# photon_pixel_shield_v1.net
KiCad netlist of a schematic drawn in EAGLE
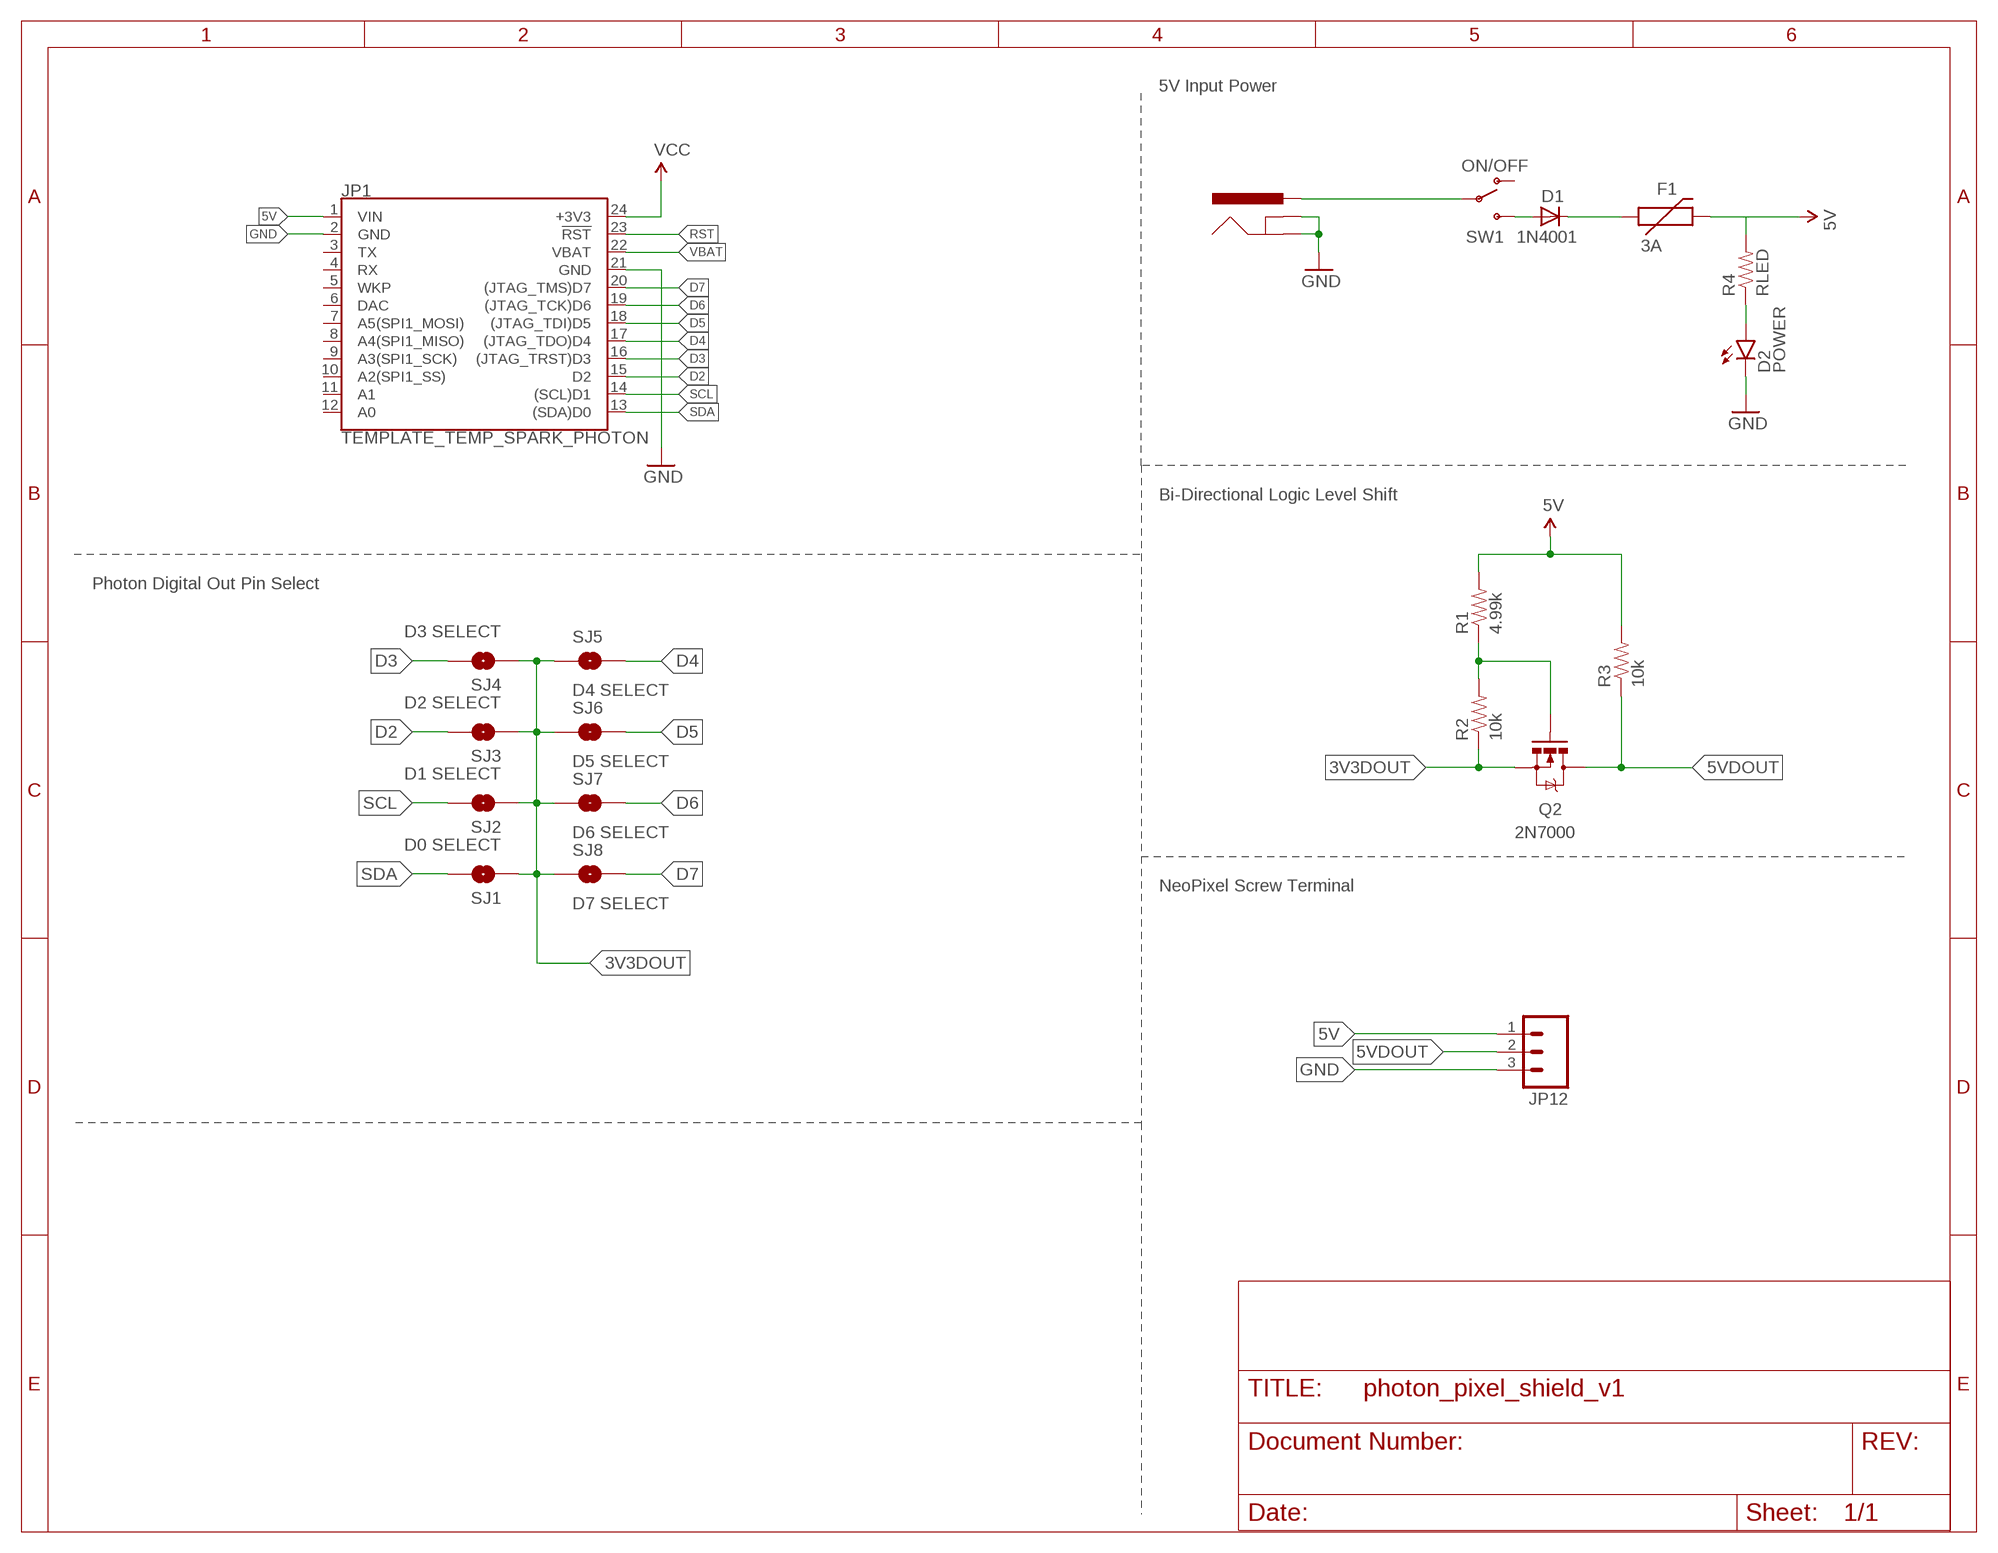
[diagram p0: schematic, sheet 1]

(export (version "E")
  (design (tool "Eeschema 10.0.6"))
  (components
    (comp (ref "D1")
      (value "1N4001")
      (footprint "eagle-import:DIODE-0.4")
      (libsource (lib "eagle-import") (part "DIODEPTH"))
    )
    (comp (ref "D2")
      (value "POWER")
      (footprint "eagle-import:LED3MM")
      (libsource (lib "eagle-import") (part "LED3MM"))
    )
    (comp (ref "F1")
      (value "3A")
      (footprint "eagle-import:PTC")
      (libsource (lib "eagle-import") (part "PTCPTH"))
    )
    (comp (ref "J1")
      (value "POWER_JACKPTH")
      (footprint "eagle-import:POWER_JACK_PTH")
      (libsource (lib "eagle-import") (part "POWER_JACKPTH"))
    )
    (comp (ref "JP1")
      (value "TEMPLATE_TEMP_SPARK_PHOTON")
      (footprint "eagle-import:TEMPLATE_TEMP_SPARK_PHOTON")
      (libsource (lib "eagle-import") (part "TEMPLATE_TEMP_SPARK_PHOTON"))
    )
    (comp (ref "JP12")
      (value "M03SCREW")
      (footprint "eagle-import:SCREWTERMINAL-3.5MM-3")
      (libsource (lib "eagle-import") (part "M03SCREW"))
    )
    (comp (ref "Q2")
      (value "2N7000")
      (footprint "eagle-import:TO-92")
      (libsource (lib "eagle-import") (part "MOSFET-NCHANNEL2N7000"))
    )
    (comp (ref "R1")
      (value "4.99k")
      (footprint "eagle-import:AXIAL-0.3")
      (libsource (lib "eagle-import") (part "10KOHM-1/4W-1%(PTH)HORIZ"))
    )
    (comp (ref "R2")
      (value "10k")
      (footprint "eagle-import:AXIAL-0.3")
      (libsource (lib "eagle-import") (part "10KOHM-1/4W-1%(PTH)HORIZ"))
    )
    (comp (ref "R3")
      (value "10k")
      (footprint "eagle-import:AXIAL-0.3")
      (libsource (lib "eagle-import") (part "10KOHM-1/4W-1%(PTH)HORIZ"))
    )
    (comp (ref "R4")
      (value "RLED")
      (footprint "eagle-import:AXIAL-0.3")
      (libsource (lib "eagle-import") (part "10KOHM-1/4W-1%(PTH)HORIZ"))
    )
    (comp (ref "SJ1")
      (value "D0 SELECT")
      (footprint "eagle-import:SJ_2S-NO")
      (libsource (lib "eagle-import") (part "SOLDERJUMPERNO"))
    )
    (comp (ref "SJ2")
      (value "D1 SELECT")
      (footprint "eagle-import:SJ_2S-NO")
      (libsource (lib "eagle-import") (part "SOLDERJUMPERNO"))
    )
    (comp (ref "SJ3")
      (value "D2 SELECT")
      (footprint "eagle-import:SJ_2S-NO")
      (libsource (lib "eagle-import") (part "SOLDERJUMPERNO"))
    )
    (comp (ref "SJ4")
      (value "D3 SELECT")
      (footprint "eagle-import:SJ_2S-NO")
      (libsource (lib "eagle-import") (part "SOLDERJUMPERNO"))
    )
    (comp (ref "SJ5")
      (value "D4 SELECT")
      (footprint "eagle-import:SJ_2S-NO")
      (libsource (lib "eagle-import") (part "SOLDERJUMPERNO"))
    )
    (comp (ref "SJ6")
      (value "D5 SELECT")
      (footprint "eagle-import:SJ_2S-NO")
      (libsource (lib "eagle-import") (part "SOLDERJUMPERNO"))
    )
    (comp (ref "SJ7")
      (value "D6 SELECT")
      (footprint "eagle-import:SJ_2S-NO")
      (libsource (lib "eagle-import") (part "SOLDERJUMPERNO"))
    )
    (comp (ref "SJ8")
      (value "D7 SELECT")
      (footprint "eagle-import:SJ_2S-NO")
      (libsource (lib "eagle-import") (part "SOLDERJUMPERNO"))
    )
    (comp (ref "SW1")
      (value "ON/OFF")
      (footprint "eagle-import:SWITCH-SPST")
      (libsource (lib "eagle-import") (part "SWITCH-SPSTPTH"))
    )
  )
  (nets
    (net (code "1") (name "3V3DOUT") (class "Default")
      (node (ref "Q2") (pin "1") (pinfunction "S_1") (pintype "passive"))
      (node (ref "R2") (pin "P$1") (pinfunction "1_P$1") (pintype "passive"))
      (node (ref "SJ1") (pin "1") (pinfunction "1_1") (pintype "passive"))
      (node (ref "SJ2") (pin "1") (pinfunction "1_1") (pintype "passive"))
      (node (ref "SJ3") (pin "1") (pinfunction "1_1") (pintype "passive"))
      (node (ref "SJ4") (pin "1") (pinfunction "1_1") (pintype "passive"))
      (node (ref "SJ5") (pin "1") (pinfunction "1_1") (pintype "passive"))
      (node (ref "SJ6") (pin "1") (pinfunction "1_1") (pintype "passive"))
      (node (ref "SJ7") (pin "1") (pinfunction "1_1") (pintype "passive"))
      (node (ref "SJ8") (pin "1") (pinfunction "1_1") (pintype "passive"))
    )
    (net (code "2") (name "5V") (class "Default")
      (node (ref "F1") (pin "P$2") (pinfunction "2_P$2") (pintype "bidirectional"))
      (node (ref "JP1") (pin "1") (pinfunction "VIN_1") (pintype "bidirectional"))
      (node (ref "JP12") (pin "1") (pinfunction "1_1") (pintype "passive"))
      (node (ref "R1") (pin "P$2") (pinfunction "2_P$2") (pintype "passive"))
      (node (ref "R3") (pin "P$2") (pinfunction "2_P$2") (pintype "passive"))
      (node (ref "R4") (pin "P$2") (pinfunction "2_P$2") (pintype "passive"))
    )
    (net (code "3") (name "5VDOUT") (class "Default")
      (node (ref "JP12") (pin "2") (pinfunction "2_2") (pintype "passive"))
      (node (ref "Q2") (pin "3") (pinfunction "D_3") (pintype "passive"))
      (node (ref "R3") (pin "P$1") (pinfunction "1_P$1") (pintype "passive"))
    )
    (net (code "4") (name "D2") (class "Default")
      (node (ref "JP1") (pin "15") (pinfunction "D2_15") (pintype "bidirectional"))
      (node (ref "SJ3") (pin "2") (pinfunction "2_2") (pintype "passive"))
    )
    (net (code "5") (name "D3") (class "Default")
      (node (ref "JP1") (pin "16") (pinfunction "(JTAG_TRST)D3_16") (pintype "bidirectional"))
      (node (ref "SJ4") (pin "2") (pinfunction "2_2") (pintype "passive"))
    )
    (net (code "6") (name "D4") (class "Default")
      (node (ref "JP1") (pin "17") (pinfunction "(JTAG_TDO)D4_17") (pintype "bidirectional"))
      (node (ref "SJ5") (pin "2") (pinfunction "2_2") (pintype "passive"))
    )
    (net (code "7") (name "D5") (class "Default")
      (node (ref "JP1") (pin "18") (pinfunction "(JTAG_TDI)D5_18") (pintype "bidirectional"))
      (node (ref "SJ6") (pin "2") (pinfunction "2_2") (pintype "passive"))
    )
    (net (code "8") (name "D6") (class "Default")
      (node (ref "JP1") (pin "19") (pinfunction "(JTAG_TCK)D6_19") (pintype "bidirectional"))
      (node (ref "SJ7") (pin "2") (pinfunction "2_2") (pintype "passive"))
    )
    (net (code "9") (name "D7") (class "Default")
      (node (ref "JP1") (pin "20") (pinfunction "(JTAG_TMS)D7_20") (pintype "bidirectional"))
      (node (ref "SJ8") (pin "2") (pinfunction "2_2") (pintype "passive"))
    )
    (net (code "10") (name "GND") (class "Default")
      (node (ref "D2") (pin "K") (pinfunction "C_K") (pintype "passive"))
      (node (ref "J1") (pin "GND") (pinfunction "GND_GND") (pintype "bidirectional"))
      (node (ref "J1") (pin "GNDBREAK") (pinfunction "GNDBREAK_GNDBREAK") (pintype "bidirectional"))
      (node (ref "JP1") (pin "2") (pinfunction "GND_2") (pintype "bidirectional"))
      (node (ref "JP1") (pin "21") (pinfunction "GND_21") (pintype "bidirectional"))
      (node (ref "JP12") (pin "3") (pinfunction "3_3") (pintype "passive"))
    )
    (net (code "11") (name "Net-(F1-1)") (class "Default")
      (node (ref "D1") (pin "C") (pinfunction "C_C") (pintype "passive"))
      (node (ref "F1") (pin "P$1") (pinfunction "1_P$1") (pintype "bidirectional"))
    )
    (net (code "12") (name "Net-(Q2-G)") (class "Default")
      (node (ref "Q2") (pin "2") (pinfunction "G_2") (pintype "passive"))
      (node (ref "R1") (pin "P$1") (pinfunction "1_P$1") (pintype "passive"))
      (node (ref "R2") (pin "P$2") (pinfunction "2_P$2") (pintype "passive"))
    )
    (net (code "13") (name "Net-(R4-1)") (class "Default")
      (node (ref "D2") (pin "A") (pinfunction "A_A") (pintype "passive"))
      (node (ref "R4") (pin "P$1") (pinfunction "1_P$1") (pintype "passive"))
    )
    (net (code "14") (name "Net-(SW1-P)") (class "Default")
      (node (ref "J1") (pin "PWR") (pinfunction "PWR_PWR") (pintype "bidirectional"))
      (node (ref "SW1") (pin "2") (pinfunction "P_2") (pintype "passive"))
    )
    (net (code "15") (name "Net-(SW1-S)") (class "Default")
      (node (ref "D1") (pin "A") (pinfunction "A_A") (pintype "passive"))
      (node (ref "SW1") (pin "3") (pinfunction "S_3") (pintype "passive"))
    )
    (net (code "16") (name "RST") (class "Default")
      (node (ref "JP1") (pin "23") (pinfunction "~{RST}_23") (pintype "bidirectional"))
    )
    (net (code "17") (name "SCL") (class "Default")
      (node (ref "JP1") (pin "14") (pinfunction "(SCL)D1_14") (pintype "bidirectional"))
      (node (ref "SJ2") (pin "2") (pinfunction "2_2") (pintype "passive"))
    )
    (net (code "18") (name "SDA") (class "Default")
      (node (ref "JP1") (pin "13") (pinfunction "(SDA)D0_13") (pintype "bidirectional"))
      (node (ref "SJ1") (pin "2") (pinfunction "2_2") (pintype "passive"))
    )
    (net (code "19") (name "VBAT") (class "Default")
      (node (ref "JP1") (pin "22") (pinfunction "VBAT_22") (pintype "bidirectional"))
    )
    (net (code "20") (name "VCC") (class "Default")
      (node (ref "JP1") (pin "24") (pinfunction "+3V3_24") (pintype "bidirectional"))
    )
    (net (code "21") (name "unconnected-(JP1-A0-Pad12)") (class "Default")
      (node (ref "JP1") (pin "12") (pinfunction "A0_12") (pintype "bidirectional"))
    )
    (net (code "22") (name "unconnected-(JP1-A1-Pad11)") (class "Default")
      (node (ref "JP1") (pin "11") (pinfunction "A1_11") (pintype "bidirectional"))
    )
    (net (code "23") (name "unconnected-(JP1-A2(SPI1_SS)-Pad10)") (class "Default")
      (node (ref "JP1") (pin "10") (pinfunction "A2(SPI1_SS)_10") (pintype "bidirectional"))
    )
    (net (code "24") (name "unconnected-(JP1-A3(SPI1_SCK)-Pad9)") (class "Default")
      (node (ref "JP1") (pin "9") (pinfunction "A3(SPI1_SCK)_9") (pintype "bidirectional"))
    )
    (net (code "25") (name "unconnected-(JP1-A4(SPI1_MISO)-Pad8)") (class "Default")
      (node (ref "JP1") (pin "8") (pinfunction "A4(SPI1_MISO)_8") (pintype "bidirectional"))
    )
    (net (code "26") (name "unconnected-(JP1-A5(SPI1_MOSI)-Pad7)") (class "Default")
      (node (ref "JP1") (pin "7") (pinfunction "A5(SPI1_MOSI)_7") (pintype "bidirectional"))
    )
    (net (code "27") (name "unconnected-(JP1-DAC-Pad6)") (class "Default")
      (node (ref "JP1") (pin "6") (pinfunction "DAC_6") (pintype "bidirectional"))
    )
    (net (code "28") (name "unconnected-(JP1-RX-Pad4)") (class "Default")
      (node (ref "JP1") (pin "4") (pinfunction "RX_4") (pintype "bidirectional"))
    )
    (net (code "29") (name "unconnected-(JP1-TX-Pad3)") (class "Default")
      (node (ref "JP1") (pin "3") (pinfunction "TX_3") (pintype "bidirectional"))
    )
    (net (code "30") (name "unconnected-(JP1-WKP-Pad5)") (class "Default")
      (node (ref "JP1") (pin "5") (pinfunction "WKP_5") (pintype "bidirectional"))
    )
    (net (code "31") (name "unconnected-(SW1-O-Pad1)") (class "Default")
      (node (ref "SW1") (pin "1") (pinfunction "O_1") (pintype "passive"))
    )
  )
)
